# 2_MCU.net
KiCad netlist of a schematic drawn in Altium Designer
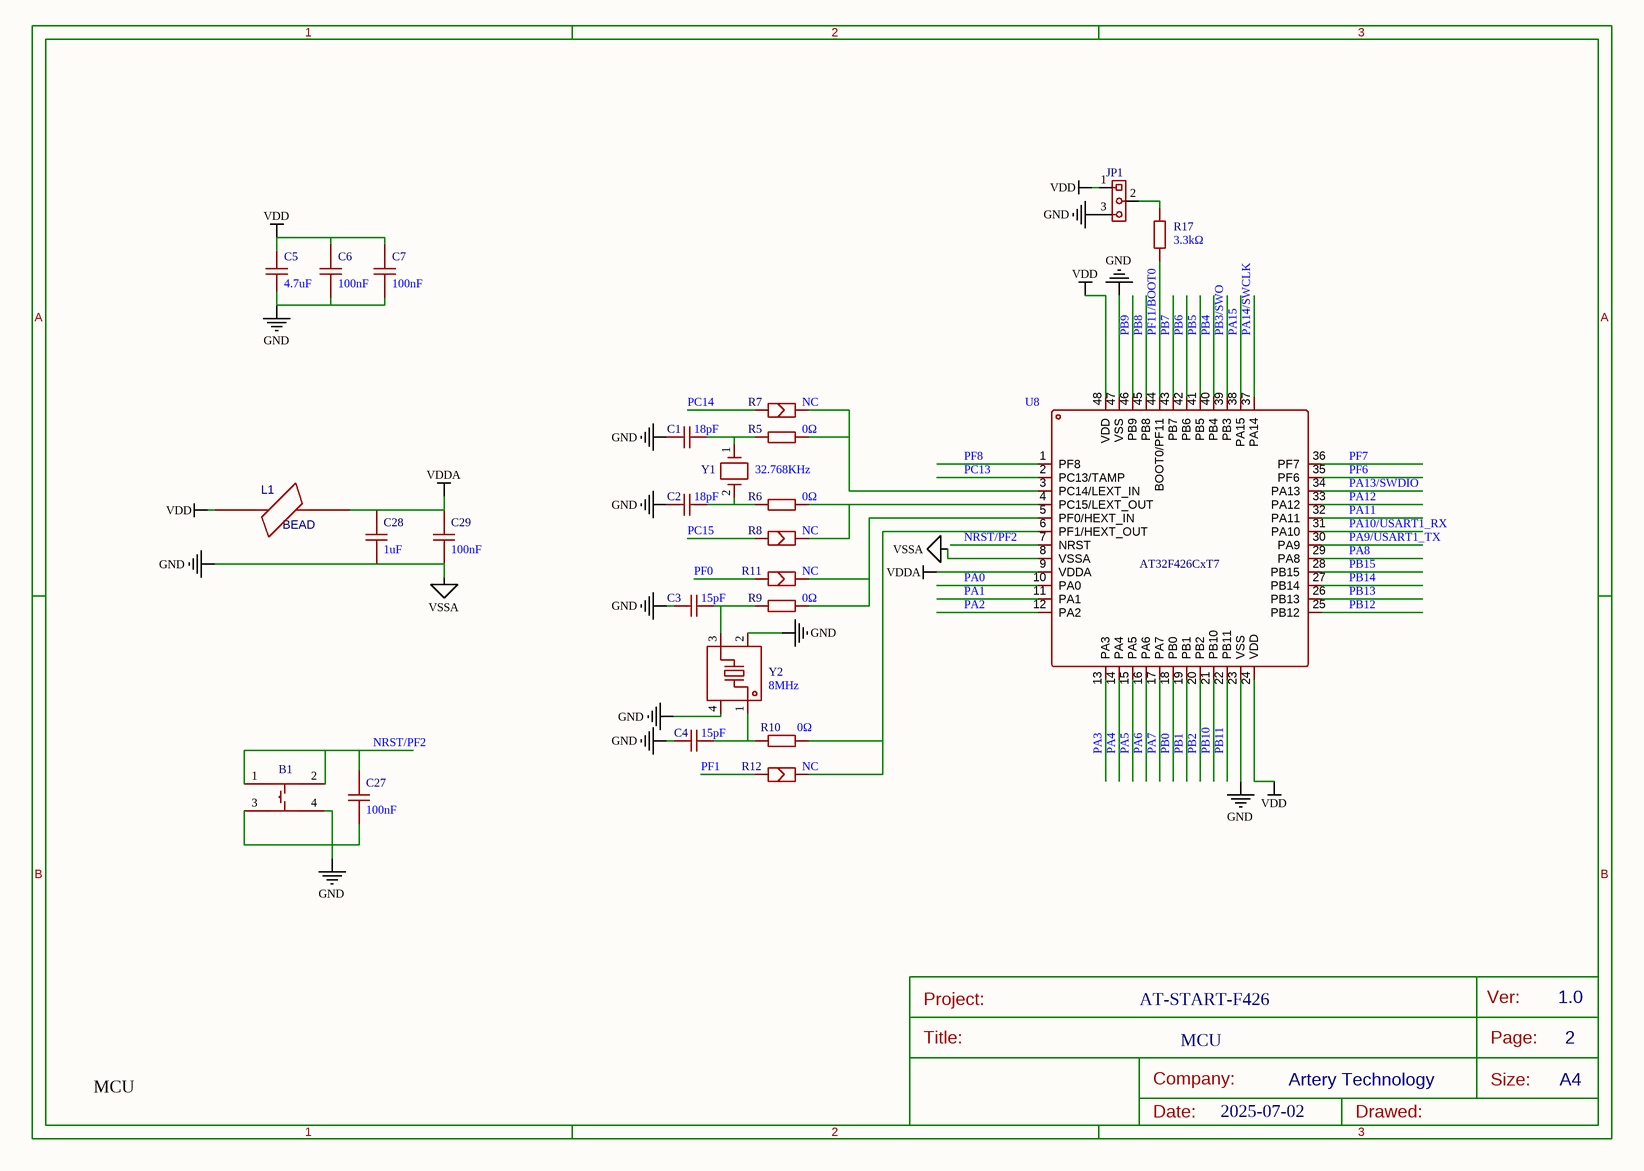
[diagram p0: 2_MCU.schdoc]

(export (version "E")
  (design (tool "Eeschema 10.0.6"))
  (components
    (comp (ref "B1")
      (value "TS-1002S-05026C")
      (footprint "KEY-SMD_4P-L6.0-W6.0-P4.50-LS9.0")
      (fields (field (name "MANUFACTURER") "XUNPU(讯普)"))
      (libsource (lib "altium-import") (part "root_0_TS-1002S-05026C_"))
    )
    (comp (ref "C1")
      (value "18pF")
      (footprint "C0603")
      (fields
        (field (name "MANUFACTURER") "SAMSUNG(三星)")
        (field (name "MANUFACTURER PART") "CL10C180JB8NNNC")
        (field (name "TOLERANCE") "±5%")
      )
      (libsource (lib "altium-import") (part "root_0_CL10C180JB8NNNC_"))
    )
    (comp (ref "C2")
      (value "18pF")
      (footprint "C0603")
      (fields
        (field (name "MANUFACTURER") "SAMSUNG(三星)")
        (field (name "MANUFACTURER PART") "CL10C180JB8NNNC")
        (field (name "TOLERANCE") "±5%")
      )
      (libsource (lib "altium-import") (part "root_0_CL10C180JB8NNNC_"))
    )
    (comp (ref "C3")
      (value "15pF")
      (footprint "C0603")
      (fields
        (field (name "MANUFACTURER") "SAMSUNG(三星)")
        (field (name "MANUFACTURER PART") "CL10C150JB8NNNC")
        (field (name "TOLERANCE") "±5%")
      )
      (libsource (lib "altium-import") (part "root_0_CL10C150JB8NNNC_"))
    )
    (comp (ref "C4")
      (value "15pF")
      (footprint "C0603")
      (fields
        (field (name "MANUFACTURER") "SAMSUNG(三星)")
        (field (name "MANUFACTURER PART") "CL10C150JB8NNNC")
        (field (name "TOLERANCE") "±5%")
      )
      (libsource (lib "altium-import") (part "root_0_CL10C150JB8NNNC_"))
    )
    (comp (ref "C5")
      (value "4.7uF")
      (footprint "C0603")
      (fields
        (field (name "MANUFACTURER PART") "CL10A475KO8NNNC")
        (field (name "MANUFACTURER") "SAMSUNG(三星)")
        (field (name "TOLERANCE") "±10%")
      )
      (libsource (lib "altium-import") (part "root_1_CL10A475KO8NNNC_"))
    )
    (comp (ref "C6")
      (value "100nF")
      (footprint "C0603")
      (fields
        (field (name "MANUFACTURER") "YAGEO(国巨)")
        (field (name "MANUFACTURER PART") "CC0603KRX7R9BB104")
        (field (name "TOLERANCE") "±10%")
      )
      (libsource (lib "altium-import") (part "root_1_CC0603KRX7R9BB104_"))
    )
    (comp (ref "C7")
      (value "100nF")
      (footprint "C0603")
      (fields
        (field (name "MANUFACTURER") "YAGEO(国巨)")
        (field (name "MANUFACTURER PART") "CC0603KRX7R9BB104")
        (field (name "TOLERANCE") "±10%")
      )
      (libsource (lib "altium-import") (part "root_1_CC0603KRX7R9BB104_"))
    )
    (comp (ref "C27")
      (value "100nF")
      (footprint "C0603")
      (fields
        (field (name "MANUFACTURER") "YAGEO(国巨)")
        (field (name "MANUFACTURER PART") "CC0603KRX7R9BB104")
        (field (name "TOLERANCE") "±10%")
      )
      (libsource (lib "altium-import") (part "root_1_CC0603KRX7R9BB104_"))
    )
    (comp (ref "C28")
      (value "1uF")
      (footprint "C0603")
      (fields
        (field (name "MANUFACTURER") "YAGEO(国巨)")
        (field (name "MANUFACTURER PART") "CC0603KRX7R9BB104")
        (field (name "TOLERANCE") "±10%")
      )
      (libsource (lib "altium-import") (part "root_1_CC0603KRX7R9BB104_"))
    )
    (comp (ref "C29")
      (value "100nF")
      (footprint "C0603")
      (fields
        (field (name "MANUFACTURER") "YAGEO(国巨)")
        (field (name "MANUFACTURER PART") "CC0603KRX7R9BB104")
        (field (name "TOLERANCE") "±10%")
      )
      (libsource (lib "altium-import") (part "root_1_CC0603KRX7R9BB104_"))
    )
    (comp (ref "JP1")
      (value "2.54-1*3P针")
      (footprint "HDR-TH_3P-P2.54-V-M-1")
      (fields (field (name "MANUFACTURER") "BOOMELE(博穆精密)"))
      (libsource (lib "altium-import") (part "root_0_2.54-1*3P针_"))
    )
    (comp (ref "L1")
      (value "BEAD")
      (footprint "r0603")
      (libsource (lib "altium-import") (part "root_0_BEAD_"))
    )
    (comp (ref "R5")
      (value "0Ω")
      (footprint "SB-PAD_2")
      (fields
        (field (name "MANUFACTURER") "UNI-ROYAL(厚声)")
        (field (name "MANUFACTURER PART") "0603WAF0000T5E")
        (field (name "TOLERANCE") "±1%")
      )
      (libsource (lib "altium-import") (part "root_0_0603WAF0000T5E_"))
    )
    (comp (ref "R6")
      (value "0Ω")
      (footprint "SB-PAD_2")
      (fields
        (field (name "MANUFACTURER") "UNI-ROYAL(厚声)")
        (field (name "MANUFACTURER PART") "0603WAF0000T5E")
        (field (name "TOLERANCE") "±1%")
      )
      (libsource (lib "altium-import") (part "root_0_0603WAF0000T5E_"))
    )
    (comp (ref "R7")
      (value "NC")
      (footprint "SB-PAD_2")
      (libsource (lib "altium-import") (part "root_0_SB_PAD_"))
    )
    (comp (ref "R8")
      (value "NC")
      (footprint "SB-PAD_2")
      (libsource (lib "altium-import") (part "root_0_SB_PAD_"))
    )
    (comp (ref "R9")
      (value "0Ω")
      (footprint "SB-PAD_2")
      (fields
        (field (name "MANUFACTURER") "UNI-ROYAL(厚声)")
        (field (name "MANUFACTURER PART") "0603WAF0000T5E")
        (field (name "TOLERANCE") "±1%")
      )
      (libsource (lib "altium-import") (part "root_0_0603WAF0000T5E_"))
    )
    (comp (ref "R10")
      (value "0Ω")
      (footprint "SB-PAD_2")
      (fields
        (field (name "MANUFACTURER") "UNI-ROYAL(厚声)")
        (field (name "MANUFACTURER PART") "0603WAF0000T5E")
        (field (name "TOLERANCE") "±1%")
      )
      (libsource (lib "altium-import") (part "root_0_0603WAF0000T5E_"))
    )
    (comp (ref "R11")
      (value "NC")
      (footprint "SB-PAD_2")
      (libsource (lib "altium-import") (part "root_0_SB_PAD_"))
    )
    (comp (ref "R12")
      (value "NC")
      (footprint "SB-PAD_2")
      (libsource (lib "altium-import") (part "root_0_SB_PAD_"))
    )
    (comp (ref "R17")
      (value "3.3kΩ")
      (footprint "R0603")
      (fields
        (field (name "MANUFACTURER") "UNI-ROYAL(厚声)")
        (field (name "MANUFACTURER PART") "0603WAF3301T5E")
        (field (name "TOLERANCE") "±1%")
      )
      (libsource (lib "altium-import") (part "root_1_0603WAF3301T5E_"))
    )
    (comp (ref "U8")
      (value "~")
      (footprint "LQFP-48_L7.0-W7.0-P0.50-LS9.0-BL")
      (fields (field (name "DEVICE") "AT32F426CxT7") (field (name "MANUFACTURER") "Artery Technology"))
      (libsource (lib "altium-import") (part "root_0_AT32F426CxT7_"))
    )
    (comp (ref "Y1")
      (value "32.768KHz")
      (footprint "XTAL_SOP - FC-12M")
      (libsource (lib "altium-import") (part "root_3_mirrored_32.768KHz_"))
    )
    (comp (ref "Y2")
      (value "8MHz")
      (footprint "CRYSTAL-SMD_4P-L3.2-W2.5-BL")
      (fields
        (field (name "MANUFACTURER") "CJ(江苏长电/长晶)")
        (field (name "MANUFACTURER PART") "CJ13-080001210B20")
        (field (name "LIBRARY NAME") "Artery_Wanbing")
      )
      (libsource (lib "altium-import") (part "root_1_CJ13-080001210B20_"))
    )
  )
  (nets
    (net (code "1") (name "/NRST{slash}PF2") (class "Default")
      (node (ref "B1") (pin "1") (pinfunction "1_1") (pintype "passive"))
      (node (ref "B1") (pin "2") (pinfunction "2_2") (pintype "passive"))
      (node (ref "C27") (pin "2") (pinfunction "2_2") (pintype "passive"))
      (node (ref "U8") (pin "7") (pinfunction "NRST_7") (pintype "passive"))
    )
    (net (code "2") (name "/PA0") (class "Default")
      (node (ref "U8") (pin "10") (pinfunction "PA0_10") (pintype "passive"))
    )
    (net (code "3") (name "/PA1") (class "Default")
      (node (ref "U8") (pin "11") (pinfunction "PA1_11") (pintype "passive"))
    )
    (net (code "4") (name "/PA2") (class "Default")
      (node (ref "U8") (pin "12") (pinfunction "PA2_12") (pintype "passive"))
    )
    (net (code "5") (name "/PA3") (class "Default")
      (node (ref "U8") (pin "13") (pinfunction "PA3_13") (pintype "passive"))
    )
    (net (code "6") (name "/PA4") (class "Default")
      (node (ref "U8") (pin "14") (pinfunction "PA4_14") (pintype "passive"))
    )
    (net (code "7") (name "/PA5") (class "Default")
      (node (ref "U8") (pin "15") (pinfunction "PA5_15") (pintype "passive"))
    )
    (net (code "8") (name "/PA6") (class "Default")
      (node (ref "U8") (pin "16") (pinfunction "PA6_16") (pintype "passive"))
    )
    (net (code "9") (name "/PA7") (class "Default")
      (node (ref "U8") (pin "17") (pinfunction "PA7_17") (pintype "passive"))
    )
    (net (code "10") (name "/PA8") (class "Default")
      (node (ref "U8") (pin "29") (pinfunction "PA8_29") (pintype "passive"))
    )
    (net (code "11") (name "/PA9{slash}USART1_TX") (class "Default")
      (node (ref "U8") (pin "30") (pinfunction "PA9_30") (pintype "passive"))
    )
    (net (code "12") (name "/PA10{slash}USART1_RX") (class "Default")
      (node (ref "U8") (pin "31") (pinfunction "PA10_31") (pintype "passive"))
    )
    (net (code "13") (name "/PA11") (class "Default")
      (node (ref "U8") (pin "32") (pinfunction "PA11_32") (pintype "passive"))
    )
    (net (code "14") (name "/PA12") (class "Default")
      (node (ref "U8") (pin "33") (pinfunction "PA12_33") (pintype "passive"))
    )
    (net (code "15") (name "/PA13{slash}SWDIO") (class "Default")
      (node (ref "U8") (pin "34") (pinfunction "PA13_34") (pintype "passive"))
    )
    (net (code "16") (name "/PA14{slash}SWCLK") (class "Default")
      (node (ref "U8") (pin "37") (pinfunction "PA14_37") (pintype "passive"))
    )
    (net (code "17") (name "/PA15") (class "Default")
      (node (ref "U8") (pin "38") (pinfunction "PA15_38") (pintype "passive"))
    )
    (net (code "18") (name "/PB0") (class "Default")
      (node (ref "U8") (pin "18") (pinfunction "PB0_18") (pintype "passive"))
    )
    (net (code "19") (name "/PB1") (class "Default")
      (node (ref "U8") (pin "19") (pinfunction "PB1_19") (pintype "passive"))
    )
    (net (code "20") (name "/PB2") (class "Default")
      (node (ref "U8") (pin "20") (pinfunction "PB2_20") (pintype "passive"))
    )
    (net (code "21") (name "/PB3{slash}SWO") (class "Default")
      (node (ref "U8") (pin "39") (pinfunction "PB3_39") (pintype "passive"))
    )
    (net (code "22") (name "/PB4") (class "Default")
      (node (ref "U8") (pin "40") (pinfunction "PB4_40") (pintype "passive"))
    )
    (net (code "23") (name "/PB5") (class "Default")
      (node (ref "U8") (pin "41") (pinfunction "PB5_41") (pintype "passive"))
    )
    (net (code "24") (name "/PB6") (class "Default")
      (node (ref "U8") (pin "42") (pinfunction "PB6_42") (pintype "passive"))
    )
    (net (code "25") (name "/PB7") (class "Default")
      (node (ref "U8") (pin "43") (pinfunction "PB7_43") (pintype "passive"))
    )
    (net (code "26") (name "/PB8") (class "Default")
      (node (ref "U8") (pin "45") (pinfunction "PB8_45") (pintype "passive"))
    )
    (net (code "27") (name "/PB9") (class "Default")
      (node (ref "U8") (pin "46") (pinfunction "PB9_46") (pintype "passive"))
    )
    (net (code "28") (name "/PB10") (class "Default")
      (node (ref "U8") (pin "21") (pinfunction "PB10_21") (pintype "passive"))
    )
    (net (code "29") (name "/PB11") (class "Default")
      (node (ref "U8") (pin "22") (pinfunction "PB11_22") (pintype "passive"))
    )
    (net (code "30") (name "/PB12") (class "Default")
      (node (ref "U8") (pin "25") (pinfunction "PB12_25") (pintype "passive"))
    )
    (net (code "31") (name "/PB13") (class "Default")
      (node (ref "U8") (pin "26") (pinfunction "PB13_26") (pintype "passive"))
    )
    (net (code "32") (name "/PB14") (class "Default")
      (node (ref "U8") (pin "27") (pinfunction "PB14_27") (pintype "passive"))
    )
    (net (code "33") (name "/PB15") (class "Default")
      (node (ref "U8") (pin "28") (pinfunction "PB15_28") (pintype "passive"))
    )
    (net (code "34") (name "/PC13") (class "Default")
      (node (ref "U8") (pin "2") (pinfunction "PC13/TAMP_2") (pintype "passive"))
    )
    (net (code "35") (name "/PC14") (class "Default")
      (node (ref "R7") (pin "1") (pinfunction "1_1") (pintype "passive"))
    )
    (net (code "36") (name "/PC15") (class "Default")
      (node (ref "R8") (pin "1") (pinfunction "1_1") (pintype "passive"))
    )
    (net (code "37") (name "/PF0") (class "Default")
      (node (ref "R11") (pin "1") (pinfunction "1_1") (pintype "passive"))
    )
    (net (code "38") (name "/PF1") (class "Default")
      (node (ref "R12") (pin "1") (pinfunction "1_1") (pintype "passive"))
    )
    (net (code "39") (name "/PF6") (class "Default")
      (node (ref "U8") (pin "35") (pinfunction "PF6_35") (pintype "passive"))
    )
    (net (code "40") (name "/PF7") (class "Default")
      (node (ref "U8") (pin "36") (pinfunction "PF7_36") (pintype "passive"))
    )
    (net (code "41") (name "/PF8") (class "Default")
      (node (ref "U8") (pin "1") (pinfunction "PF8_1") (pintype "passive"))
    )
    (net (code "42") (name "/PF11{slash}BOOT0") (class "Default")
      (node (ref "R17") (pin "1") (pinfunction "1_1") (pintype "passive"))
      (node (ref "U8") (pin "44") (pinfunction "BOOT0/PF11_44") (pintype "passive"))
    )
    (net (code "43") (name "GND") (class "Default")
      (node (ref "B1") (pin "3") (pinfunction "3_3") (pintype "passive"))
      (node (ref "B1") (pin "4") (pinfunction "4_4") (pintype "passive"))
      (node (ref "C1") (pin "1") (pinfunction "1_1") (pintype "passive"))
      (node (ref "C2") (pin "1") (pinfunction "1_1") (pintype "passive"))
      (node (ref "C27") (pin "1") (pinfunction "1_1") (pintype "passive"))
      (node (ref "C28") (pin "1") (pinfunction "1_1") (pintype "passive"))
      (node (ref "C29") (pin "1") (pinfunction "1_1") (pintype "passive"))
      (node (ref "C3") (pin "1") (pinfunction "1_1") (pintype "passive"))
      (node (ref "C4") (pin "1") (pinfunction "1_1") (pintype "passive"))
      (node (ref "C5") (pin "1") (pinfunction "1_1") (pintype "passive"))
      (node (ref "C6") (pin "1") (pinfunction "1_1") (pintype "passive"))
      (node (ref "C7") (pin "1") (pinfunction "1_1") (pintype "passive"))
      (node (ref "JP1") (pin "3") (pinfunction "3_3") (pintype "passive"))
      (node (ref "U8") (pin "23") (pinfunction "VSS_23") (pintype "passive"))
      (node (ref "U8") (pin "47") (pinfunction "VSS_47") (pintype "passive"))
      (node (ref "U8") (pin "8") (pinfunction "VSSA_8") (pintype "passive"))
      (node (ref "Y2") (pin "2") (pinfunction "GND_2") (pintype "passive"))
      (node (ref "Y2") (pin "4") (pinfunction "GND_4") (pintype "passive"))
    )
    (net (code "44") (name "Net-(C1-Pad2)") (class "Default")
      (node (ref "C1") (pin "2") (pinfunction "2_2") (pintype "passive"))
      (node (ref "R5") (pin "1") (pinfunction "1_1") (pintype "passive"))
      (node (ref "Y1") (pin "1") (pinfunction "1_1") (pintype "passive"))
    )
    (net (code "45") (name "Net-(C2-Pad2)") (class "Default")
      (node (ref "C2") (pin "2") (pinfunction "2_2") (pintype "passive"))
      (node (ref "R6") (pin "1") (pinfunction "1_1") (pintype "passive"))
      (node (ref "Y1") (pin "2") (pinfunction "2_2") (pintype "passive"))
    )
    (net (code "46") (name "Net-(C3-Pad2)") (class "Default")
      (node (ref "C3") (pin "2") (pinfunction "2_2") (pintype "passive"))
      (node (ref "R9") (pin "1") (pinfunction "1_1") (pintype "passive"))
      (node (ref "Y2") (pin "3") (pinfunction "3_3") (pintype "passive"))
    )
    (net (code "47") (name "Net-(C4-Pad2)") (class "Default")
      (node (ref "C4") (pin "2") (pinfunction "2_2") (pintype "passive"))
      (node (ref "R10") (pin "1") (pinfunction "1_1") (pintype "passive"))
      (node (ref "Y2") (pin "1") (pinfunction "1_1") (pintype "passive"))
    )
    (net (code "48") (name "Net-(JP1-Pad2)") (class "Default")
      (node (ref "JP1") (pin "2") (pinfunction "2_2") (pintype "passive"))
      (node (ref "R17") (pin "2") (pinfunction "2_2") (pintype "passive"))
    )
    (net (code "49") (name "Net-(U8-PC14{slash}LEXT_IN)") (class "Default")
      (node (ref "R5") (pin "2") (pinfunction "2_2") (pintype "passive"))
      (node (ref "R7") (pin "2") (pinfunction "2_2") (pintype "passive"))
      (node (ref "U8") (pin "3") (pinfunction "PC14/LEXT_IN_3") (pintype "passive"))
    )
    (net (code "50") (name "Net-(U8-PC15{slash}LEXT_OUT)") (class "Default")
      (node (ref "R6") (pin "2") (pinfunction "2_2") (pintype "passive"))
      (node (ref "R8") (pin "2") (pinfunction "2_2") (pintype "passive"))
      (node (ref "U8") (pin "4") (pinfunction "PC15/LEXT_OUT_4") (pintype "passive"))
    )
    (net (code "51") (name "Net-(U8-PF0{slash}HEXT_IN)") (class "Default")
      (node (ref "R11") (pin "2") (pinfunction "2_2") (pintype "passive"))
      (node (ref "R9") (pin "2") (pinfunction "2_2") (pintype "passive"))
      (node (ref "U8") (pin "5") (pinfunction "PF0/HEXT_IN_5") (pintype "passive"))
    )
    (net (code "52") (name "Net-(U8-PF1{slash}HEXT_OUT)") (class "Default")
      (node (ref "R10") (pin "2") (pinfunction "2_2") (pintype "passive"))
      (node (ref "R12") (pin "2") (pinfunction "2_2") (pintype "passive"))
      (node (ref "U8") (pin "6") (pinfunction "PF1/HEXT_OUT_6") (pintype "passive"))
    )
    (net (code "53") (name "VDD") (class "Default")
      (node (ref "C5") (pin "2") (pinfunction "2_2") (pintype "passive"))
      (node (ref "C6") (pin "2") (pinfunction "2_2") (pintype "passive"))
      (node (ref "C7") (pin "2") (pinfunction "2_2") (pintype "passive"))
      (node (ref "JP1") (pin "1") (pinfunction "1_1") (pintype "passive"))
      (node (ref "L1") (pin "1") (pinfunction "1_1") (pintype "passive"))
      (node (ref "U8") (pin "24") (pinfunction "VDD_24") (pintype "passive"))
      (node (ref "U8") (pin "48") (pinfunction "VDD_48") (pintype "passive"))
    )
    (net (code "54") (name "VDDA") (class "Default")
      (node (ref "C28") (pin "2") (pinfunction "2_2") (pintype "passive"))
      (node (ref "C29") (pin "2") (pinfunction "2_2") (pintype "passive"))
      (node (ref "L1") (pin "2") (pinfunction "2_2") (pintype "passive"))
      (node (ref "U8") (pin "9") (pinfunction "VDDA_9") (pintype "passive"))
    )
  )
)
